# TmpLightHumBaro.net
KiCad netlist of a schematic drawn in Altium Designer
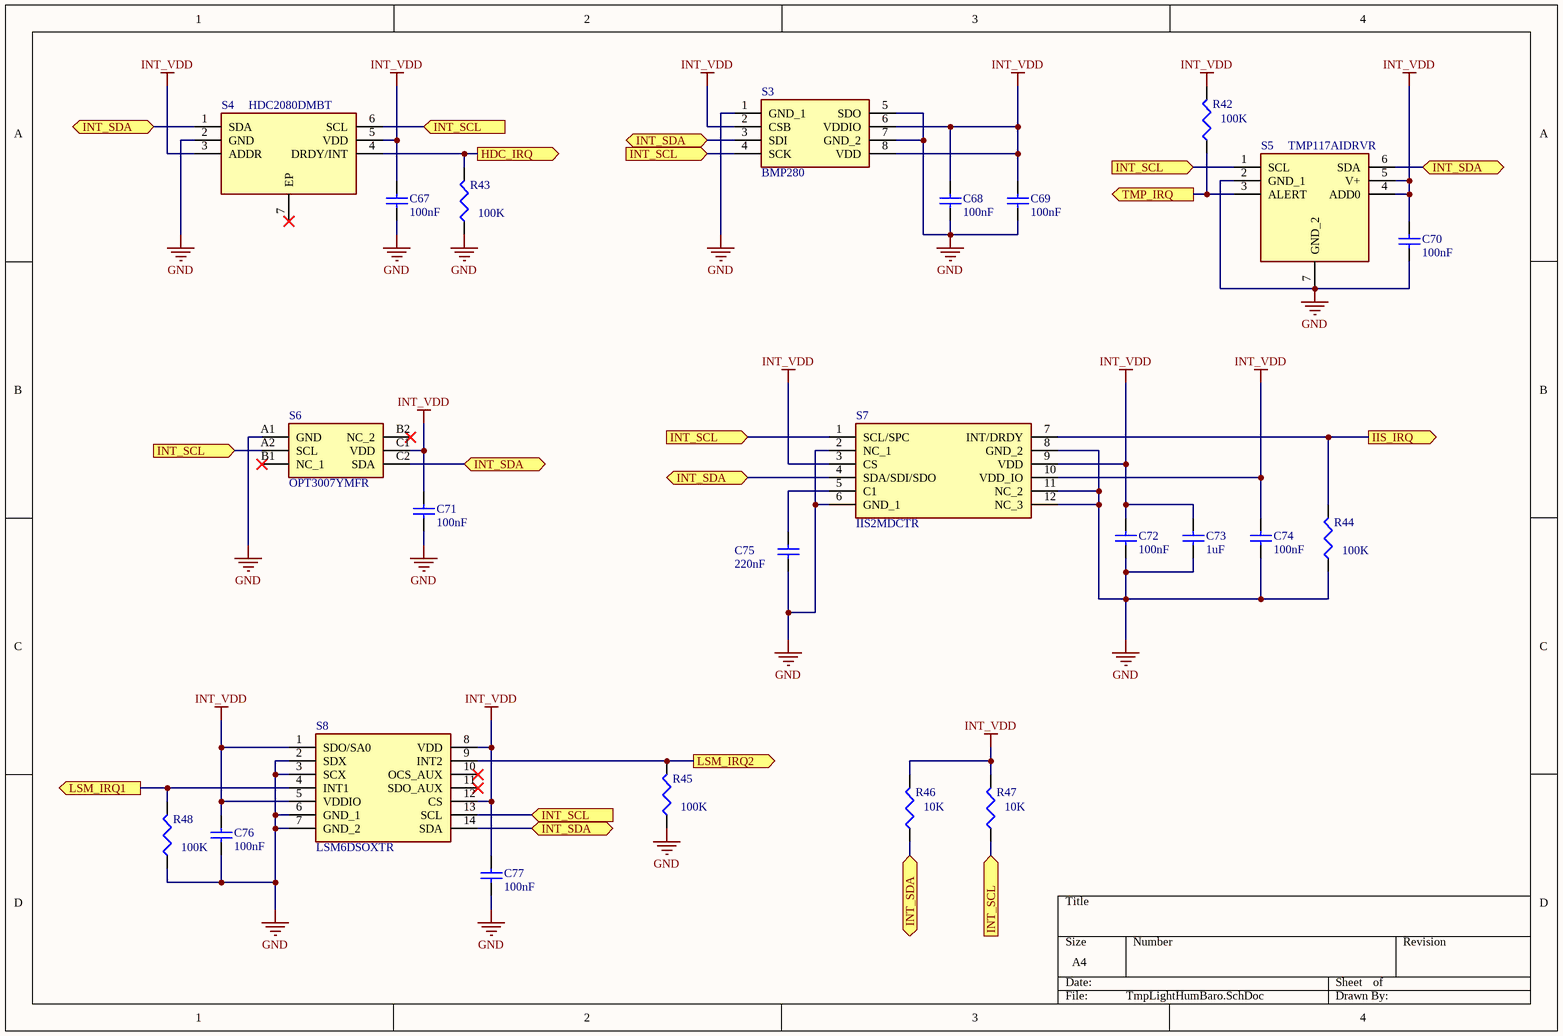
[diagram p0: TmpLightHumBaro.SchDoc]

(export (version "E")
  (design (tool "Eeschema 10.0.6"))
  (components
    (comp (ref "C67")
      (value "100nF")
      (footprint "CAPC1608X90X35NL10T15")
      (fields (field (name "PART NUMBER") "GRM188R71H102KA01D") (field (name "MANUFACTURER") "Murata"))
      (libsource (lib "Altium Content Vault") (part "CAP"))
    )
    (comp (ref "C68")
      (value "100nF")
      (footprint "CAPC1608X90X35NL10T15")
      (fields (field (name "PART NUMBER") "GRM188R71H102KA01D") (field (name "MANUFACTURER") "Murata"))
      (libsource (lib "Altium Content Vault") (part "CAP"))
    )
    (comp (ref "C69")
      (value "100nF")
      (footprint "CAPC1608X90X35NL10T15")
      (fields (field (name "PART NUMBER") "GRM188R71H102KA01D") (field (name "MANUFACTURER") "Murata"))
      (libsource (lib "Altium Content Vault") (part "CAP"))
    )
    (comp (ref "C70")
      (value "100nF")
      (footprint "CAPC1608X90X35NL10T15")
      (fields (field (name "PART NUMBER") "GRM188R71H102KA01D") (field (name "MANUFACTURER") "Murata"))
      (libsource (lib "Altium Content Vault") (part "CAP"))
    )
    (comp (ref "C71")
      (value "100nF")
      (footprint "CAPC1608X90X35NL10T15")
      (fields (field (name "PART NUMBER") "GRM188R71H102KA01D") (field (name "MANUFACTURER") "Murata"))
      (libsource (lib "Altium Content Vault") (part "CAP"))
    )
    (comp (ref "C72")
      (value "100nF")
      (footprint "CAPC1608X90X35NL10T15")
      (fields (field (name "PART NUMBER") "GRM188R71H102KA01D") (field (name "MANUFACTURER") "Murata"))
      (libsource (lib "Altium Content Vault") (part "CAP"))
    )
    (comp (ref "C73")
      (value "1uF")
      (footprint "CAPC1608X90X35NL10T15")
      (fields (field (name "PART NUMBER") "GRM188R71H102KA01D") (field (name "MANUFACTURER") "Murata"))
      (libsource (lib "Altium Content Vault") (part "CAP"))
    )
    (comp (ref "C74")
      (value "100nF")
      (footprint "CAPC1608X90X35NL10T15")
      (fields (field (name "PART NUMBER") "GRM188R71H102KA01D") (field (name "MANUFACTURER") "Murata"))
      (libsource (lib "Altium Content Vault") (part "CAP"))
    )
    (comp (ref "C75")
      (value "220nF")
      (footprint "CAPC1608X90X35NL10T15")
      (fields (field (name "PART NUMBER") "GRM188R71H102KA01D") (field (name "MANUFACTURER") "Murata"))
      (libsource (lib "Altium Content Vault") (part "CAP"))
    )
    (comp (ref "C76")
      (value "100nF")
      (footprint "CAPC1608X90X35NL10T15")
      (fields (field (name "PART NUMBER") "GRM188R71H102KA01D") (field (name "MANUFACTURER") "Murata"))
      (libsource (lib "Altium Content Vault") (part "CAP"))
    )
    (comp (ref "C77")
      (value "100nF")
      (footprint "CAPC1608X90X35NL10T15")
      (fields (field (name "PART NUMBER") "GRM188R71H102KA01D") (field (name "MANUFACTURER") "Murata"))
      (libsource (lib "Altium Content Vault") (part "CAP"))
    )
    (comp (ref "R42")
      (value "100K")
      (footprint "J1-0603")
      (description "Resistor")
      (fields (field (name "PUBLISHER") "Altium Limited"))
      (libsource (lib "Miscellaneous Devices") (part "Res3"))
    )
    (comp (ref "R43")
      (value "100K")
      (footprint "J1-0603")
      (description "Resistor")
      (fields (field (name "PUBLISHER") "Altium Limited"))
      (libsource (lib "Miscellaneous Devices") (part "Res3"))
    )
    (comp (ref "R44")
      (value "100K")
      (footprint "J1-0603")
      (description "Resistor")
      (fields (field (name "PUBLISHER") "Altium Limited"))
      (libsource (lib "Miscellaneous Devices") (part "Res3"))
    )
    (comp (ref "R45")
      (value "100K")
      (footprint "J1-0603")
      (description "Resistor")
      (fields (field (name "PUBLISHER") "Altium Limited"))
      (libsource (lib "Miscellaneous Devices") (part "Res3"))
    )
    (comp (ref "R46")
      (value "10K")
      (footprint "J1-0603")
      (description "Resistor")
      (fields (field (name "PUBLISHER") "Altium Limited"))
      (libsource (lib "Miscellaneous Devices") (part "Res3"))
    )
    (comp (ref "R47")
      (value "10K")
      (footprint "J1-0603")
      (description "Resistor")
      (fields (field (name "PUBLISHER") "Altium Limited"))
      (libsource (lib "Miscellaneous Devices") (part "Res3"))
    )
    (comp (ref "R48")
      (value "100K")
      (footprint "J1-0603")
      (description "Resistor")
      (fields (field (name "PUBLISHER") "Altium Limited"))
      (libsource (lib "Miscellaneous Devices") (part "Res3"))
    )
    (comp (ref "S3")
      (value "BMP280")
      (footprint "SamacSys:8-PIN-METAL-LID-LGA_1")
      (description "Integrated Circuit")
      (fields (field (name "MOUSER PART NUMBER") "262-BMP280"))
      (libsource (lib "*") (part "BMP280"))
    )
    (comp (ref "S4")
      (value "HDC2080DMBT")
      (footprint "SamacSys:SON100P300X300X80-7N-D")
      (description "Undefined or Miscellaneous")
      (fields
        (field (name "MOUSER PART NUMBER") "595-HDC2080DMBT")
        (field (name "RS PART NUMBER") "1797065P")
      )
      (libsource (lib "*") (part "HDC2080DMBT"))
    )
    (comp (ref "S5")
      (value "TMP117AIDRVR")
      (footprint "SamacSys:SON65P200X200X80-7N")
      (description "Integrated Circuit")
      (fields (field (name "MOUSER PART NUMBER") "595-TMP117AIDRVR"))
      (libsource (lib "*") (part "TMP117AIDRVR"))
    )
    (comp (ref "S6")
      (value "OPT3007YMFR")
      (footprint "SamacSys:BGA6C35P2X3_86X95X23")
      (description "Integrated Circuit")
      (fields (field (name "MOUSER PART NUMBER") "595-OPT3007YMFR"))
      (libsource (lib "*") (part "OPT3007YMFR"))
    )
    (comp (ref "S7")
      (value "IIS2MDCTR")
      (footprint "SamacSys:IIS2MDCTR")
      (description "Integrated Circuit")
      (fields (field (name "MOUSER PART NUMBER") "511-IIS2MDCTR"))
      (libsource (lib "*") (part "IIS2MDCTR"))
    )
    (comp (ref "S8")
      (value "LSM6DSOXTR")
      (footprint "SamacSys:LGA-14_1")
      (description "Accelerometer")
      (fields (field (name "MOUSER PART NUMBER") "511-LSM6DSOXTR"))
      (libsource (lib "*") (part "LSM6DSOXTR"))
    )
  )
  (nets
    (net (code "1") (name "/HDC_IRQ") (class "Default")
      (node (ref "R43") (pin "2") (pinfunction "2_2") (pintype "passive"))
      (node (ref "S4") (pin "4") (pinfunction "DRDY/INT_4") (pintype "passive"))
    )
    (net (code "2") (name "/IIS_IRQ") (class "Default")
      (node (ref "R44") (pin "2") (pinfunction "2_2") (pintype "passive"))
      (node (ref "S7") (pin "7") (pinfunction "INT/DRDY_7") (pintype "passive"))
    )
    (net (code "3") (name "/INT_SCL") (class "Default")
      (node (ref "R47") (pin "1") (pinfunction "1_1") (pintype "passive"))
      (node (ref "S3") (pin "4") (pinfunction "SCK_4") (pintype "passive"))
      (node (ref "S4") (pin "6") (pinfunction "SCL_6") (pintype "passive"))
      (node (ref "S5") (pin "1") (pinfunction "SCL_1") (pintype "passive"))
      (node (ref "S6") (pin "A2") (pinfunction "SCL_A2") (pintype "passive"))
      (node (ref "S7") (pin "1") (pinfunction "SCL/SPC_1") (pintype "passive"))
      (node (ref "S8") (pin "13") (pinfunction "SCL_13") (pintype "passive"))
    )
    (net (code "4") (name "/INT_SDA") (class "Default")
      (node (ref "R46") (pin "1") (pinfunction "1_1") (pintype "passive"))
      (node (ref "S3") (pin "3") (pinfunction "SDI_3") (pintype "passive"))
      (node (ref "S4") (pin "1") (pinfunction "SDA_1") (pintype "passive"))
      (node (ref "S5") (pin "6") (pinfunction "SDA_6") (pintype "passive"))
      (node (ref "S6") (pin "C2") (pinfunction "SDA_C2") (pintype "passive"))
      (node (ref "S7") (pin "4") (pinfunction "SDA/SDI/SDO_4") (pintype "passive"))
      (node (ref "S8") (pin "14") (pinfunction "SDA_14") (pintype "passive"))
    )
    (net (code "5") (name "/LSM_IRQ1") (class "Default")
      (node (ref "R48") (pin "2") (pinfunction "2_2") (pintype "passive"))
      (node (ref "S8") (pin "4") (pinfunction "INT1_4") (pintype "passive"))
    )
    (net (code "6") (name "/LSM_IRQ2") (class "Default")
      (node (ref "R45") (pin "2") (pinfunction "2_2") (pintype "passive"))
      (node (ref "S8") (pin "9") (pinfunction "INT2_9") (pintype "passive"))
    )
    (net (code "7") (name "/TMP_IRQ") (class "Default")
      (node (ref "R42") (pin "1") (pinfunction "1_1") (pintype "passive"))
      (node (ref "S5") (pin "3") (pinfunction "ALERT_3") (pintype "passive"))
    )
    (net (code "8") (name "GND") (class "Default")
      (node (ref "C67") (pin "2") (pinfunction "2_2") (pintype "passive"))
      (node (ref "C68") (pin "2") (pinfunction "2_2") (pintype "passive"))
      (node (ref "C69") (pin "2") (pinfunction "2_2") (pintype "passive"))
      (node (ref "C70") (pin "2") (pinfunction "2_2") (pintype "passive"))
      (node (ref "C71") (pin "2") (pinfunction "2_2") (pintype "passive"))
      (node (ref "C72") (pin "2") (pinfunction "2_2") (pintype "passive"))
      (node (ref "C73") (pin "2") (pinfunction "2_2") (pintype "passive"))
      (node (ref "C74") (pin "2") (pinfunction "2_2") (pintype "passive"))
      (node (ref "C75") (pin "2") (pinfunction "2_2") (pintype "passive"))
      (node (ref "C76") (pin "2") (pinfunction "2_2") (pintype "passive"))
      (node (ref "C77") (pin "2") (pinfunction "2_2") (pintype "passive"))
      (node (ref "R43") (pin "1") (pinfunction "1_1") (pintype "passive"))
      (node (ref "R44") (pin "1") (pinfunction "1_1") (pintype "passive"))
      (node (ref "R45") (pin "1") (pinfunction "1_1") (pintype "passive"))
      (node (ref "R48") (pin "1") (pinfunction "1_1") (pintype "passive"))
      (node (ref "S3") (pin "1") (pinfunction "GND_1_1") (pintype "passive"))
      (node (ref "S3") (pin "5") (pinfunction "SDO_5") (pintype "passive"))
      (node (ref "S3") (pin "7") (pinfunction "GND_2_7") (pintype "passive"))
      (node (ref "S4") (pin "2") (pinfunction "GND_2") (pintype "passive"))
      (node (ref "S5") (pin "2") (pinfunction "GND_1_2") (pintype "passive"))
      (node (ref "S5") (pin "7") (pinfunction "GND_2_7") (pintype "passive"))
      (node (ref "S6") (pin "A1") (pinfunction "GND_A1") (pintype "passive"))
      (node (ref "S7") (pin "11") (pinfunction "NC_2_11") (pintype "passive"))
      (node (ref "S7") (pin "12") (pinfunction "NC_3_12") (pintype "passive"))
      (node (ref "S7") (pin "2") (pinfunction "NC_1_2") (pintype "passive"))
      (node (ref "S7") (pin "6") (pinfunction "GND_1_6") (pintype "passive"))
      (node (ref "S7") (pin "8") (pinfunction "GND_2_8") (pintype "passive"))
      (node (ref "S8") (pin "2") (pinfunction "SDX_2") (pintype "passive"))
      (node (ref "S8") (pin "3") (pinfunction "SCX_3") (pintype "passive"))
      (node (ref "S8") (pin "6") (pinfunction "GND_1_6") (pintype "passive"))
      (node (ref "S8") (pin "7") (pinfunction "GND_2_7") (pintype "passive"))
    )
    (net (code "9") (name "INT_VDD") (class "Default")
      (node (ref "C67") (pin "1") (pinfunction "1_1") (pintype "passive"))
      (node (ref "C68") (pin "1") (pinfunction "1_1") (pintype "passive"))
      (node (ref "C69") (pin "1") (pinfunction "1_1") (pintype "passive"))
      (node (ref "C70") (pin "1") (pinfunction "1_1") (pintype "passive"))
      (node (ref "C71") (pin "1") (pinfunction "1_1") (pintype "passive"))
      (node (ref "C72") (pin "1") (pinfunction "1_1") (pintype "passive"))
      (node (ref "C73") (pin "1") (pinfunction "1_1") (pintype "passive"))
      (node (ref "C74") (pin "1") (pinfunction "1_1") (pintype "passive"))
      (node (ref "C76") (pin "1") (pinfunction "1_1") (pintype "passive"))
      (node (ref "C77") (pin "1") (pinfunction "1_1") (pintype "passive"))
      (node (ref "R42") (pin "2") (pinfunction "2_2") (pintype "passive"))
      (node (ref "R46") (pin "2") (pinfunction "2_2") (pintype "passive"))
      (node (ref "R47") (pin "2") (pinfunction "2_2") (pintype "passive"))
      (node (ref "S3") (pin "2") (pinfunction "CSB_2") (pintype "passive"))
      (node (ref "S3") (pin "6") (pinfunction "VDDIO_6") (pintype "passive"))
      (node (ref "S3") (pin "8") (pinfunction "VDD_8") (pintype "passive"))
      (node (ref "S4") (pin "3") (pinfunction "ADDR_3") (pintype "passive"))
      (node (ref "S4") (pin "5") (pinfunction "VDD_5") (pintype "passive"))
      (node (ref "S5") (pin "4") (pinfunction "ADD0_4") (pintype "passive"))
      (node (ref "S5") (pin "5") (pinfunction "V+_5") (pintype "passive"))
      (node (ref "S6") (pin "C1") (pinfunction "VDD_C1") (pintype "passive"))
      (node (ref "S7") (pin "10") (pinfunction "VDD_IO_10") (pintype "passive"))
      (node (ref "S7") (pin "3") (pinfunction "CS_3") (pintype "passive"))
      (node (ref "S7") (pin "9") (pinfunction "VDD_9") (pintype "passive"))
      (node (ref "S8") (pin "1") (pinfunction "SDO/SA0_1") (pintype "passive"))
      (node (ref "S8") (pin "12") (pinfunction "CS_12") (pintype "passive"))
      (node (ref "S8") (pin "5") (pinfunction "VDDIO_5") (pintype "passive"))
      (node (ref "S8") (pin "8") (pinfunction "VDD_8") (pintype "passive"))
    )
    (net (code "10") (name "Net-(S7-C1)") (class "Default")
      (node (ref "C75") (pin "1") (pinfunction "1_1") (pintype "passive"))
      (node (ref "S7") (pin "5") (pinfunction "C1_5") (pintype "passive"))
    )
    (net (code "11") (name "unconnected-(S4-EP-Pad7)") (class "Default")
      (node (ref "S4") (pin "7") (pinfunction "EP_7") (pintype "passive+no_connect"))
    )
    (net (code "12") (name "unconnected-(S6-NC_1-PadB1)") (class "Default")
      (node (ref "S6") (pin "B1") (pinfunction "NC_1_B1") (pintype "passive+no_connect"))
    )
    (net (code "13") (name "unconnected-(S6-NC_2-PadB2)") (class "Default")
      (node (ref "S6") (pin "B2") (pinfunction "NC_2_B2") (pintype "passive+no_connect"))
    )
    (net (code "14") (name "unconnected-(S8-OCS_AUX-Pad10)") (class "Default")
      (node (ref "S8") (pin "10") (pinfunction "OCS_AUX_10") (pintype "passive+no_connect"))
    )
    (net (code "15") (name "unconnected-(S8-SDO_AUX-Pad11)") (class "Default")
      (node (ref "S8") (pin "11") (pinfunction "SDO_AUX_11") (pintype "passive+no_connect"))
    )
  )
)
